# 1_MLink_V13.net
KiCad netlist of a schematic drawn in Altium Designer
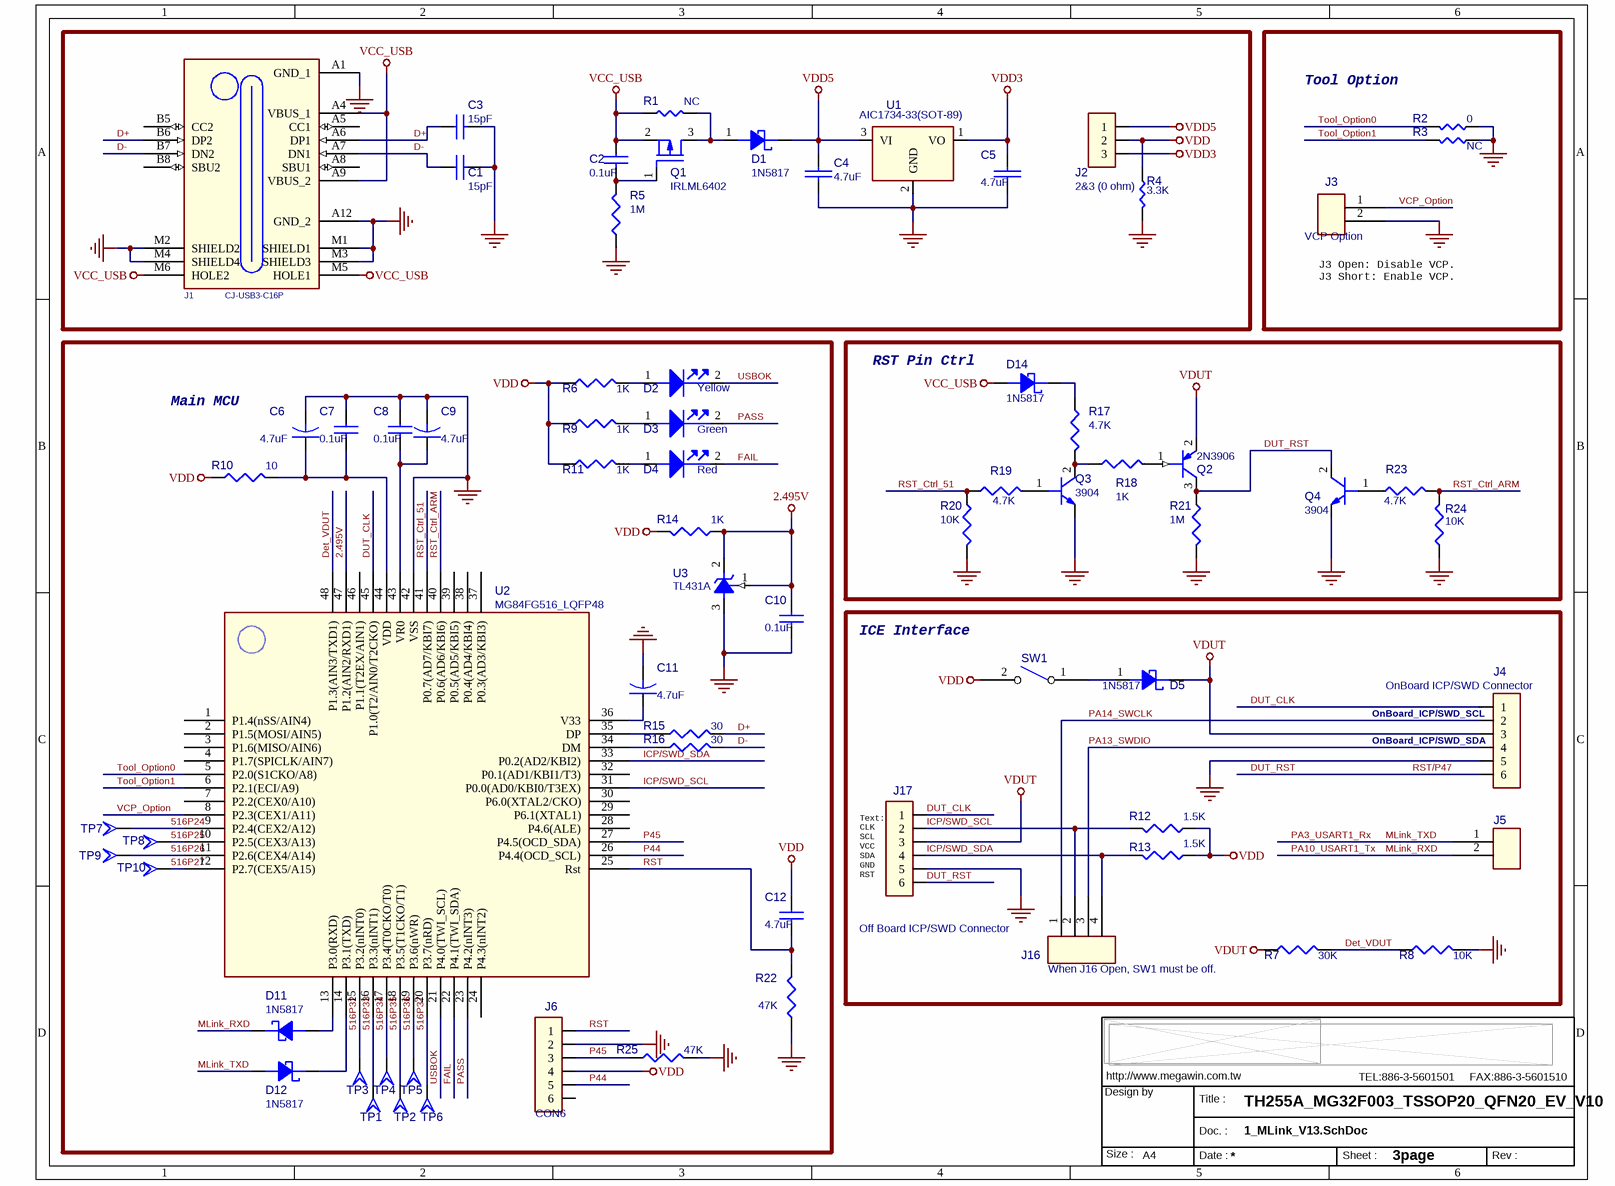
[diagram p0: 1_MLink_V13.SchDoc]

(export (version "E")
  (design (tool "Eeschema 10.0.6"))
  (components
    (comp (ref "C1") (value "15pF") (footprint "0603C") (libsource (lib "") (part "CAP NP_Dup1_1")))
    (comp (ref "C2") (value "0.1uF") (footprint "0603C") (libsource (lib "*") (part "CAP NP")))
    (comp (ref "C3") (value "15pF") (footprint "0603C") (libsource (lib "*") (part "CAP NP_Dup1")))
    (comp (ref "C4") (value "4.7uF") (footprint "0805C") (libsource (lib "*") (part "C NP")))
    (comp (ref "C5") (value "4.7uF") (footprint "0805C") (libsource (lib "*") (part "C NP")))
    (comp (ref "C6") (value "4.7uF") (libsource (lib "*") (part "CAP")))
    (comp (ref "C7") (value "0.1uF") (footprint "0603C") (libsource (lib "*") (part "CAP NP_Dup1")))
    (comp (ref "C8") (value "0.1uF") (footprint "0603C") (libsource (lib "*") (part "CAP NP")))
    (comp (ref "C9") (value "4.7uF") (libsource (lib "") (part "CAP_1")))
    (comp (ref "C10") (value "0.1uF") (footprint "0603C") (libsource (lib "*") (part "CAP NP")))
    (comp (ref "C11") (value "4.7uF") (footprint "0805C") (libsource (lib "") (part "CAP_1")))
    (comp (ref "C12") (value "4.7uF") (footprint "0805C") (libsource (lib "*") (part "CAP NP_Dup1")))
    (comp (ref "D1")
      (value "1N5817")
      (footprint "DIODE_SMA_SOD323")
      (libsource (lib "") (part "DIODE SCHOTTKY_1"))
    )
    (comp (ref "D2") (value "Yellow") (libsource (lib "*") (part "Led0_0")))
    (comp (ref "D3") (value "Green") (libsource (lib "*") (part "Led0_0")))
    (comp (ref "D4") (value "Red") (libsource (lib "*") (part "Led0_0")))
    (comp (ref "D5")
      (value "1N5817")
      (footprint "DIODE_SMA_SOD323")
      (libsource (lib "") (part "DIODE SCHOTTKY_1"))
    )
    (comp (ref "D11")
      (value "1N5817")
      (footprint "DIODE_SMA_SOD323")
      (libsource (lib "*") (part "DIODE SCHOTTKY"))
    )
    (comp (ref "D12")
      (value "1N5817")
      (footprint "DIODE_SMA_SOD323")
      (libsource (lib "*") (part "DIODE SCHOTTKY"))
    )
    (comp (ref "D14")
      (value "1N5817")
      (footprint "DIODE_SMA_SOD323")
      (libsource (lib "*") (part "DIODE SCHOTTKY"))
    )
    (comp (ref "J1")
      (value "CJ-USB3-C16P")
      (footprint "USB_CF_16_SMD")
      (description "TPYE-C-9")
      (libsource (lib "*") (part "CJ-USB3-C16P"))
    )
    (comp (ref "J2") (value "2&3 (0 ohm)") (footprint "PS3P254") (libsource (lib "*") (part "CON3")))
    (comp (ref "J3") (value "VCP Option") (footprint "PS2P254") (libsource (lib "*") (part "CON2")))
    (comp (ref "J4")
      (value "OnBoard ICP/SWD Connector")
      (footprint "PS6P254")
      (libsource (lib "*") (part "CON6"))
    )
    (comp (ref "J5") (value "NC") (footprint "PS2P254") (libsource (lib "") (part "CON2_1")))
    (comp (ref "J6") (value "CON6") (footprint "PS6P254") (libsource (lib "") (part "CON6_1")))
    (comp (ref "J16")
      (value "When J16 Open, SW1 must be off.")
      (footprint "PS4P254")
      (libsource (lib "*") (part "CON4"))
    )
    (comp (ref "J17")
      (value "Off Board ICP/SWD Connector")
      (footprint "PS6P254_90")
      (libsource (lib "") (part "CON6_1"))
    )
    (comp (ref "MW1")
      (value "MW-A4")
      (footprint "MEGAWIN_3.4_1")
      (fields
        (field (name "ORGADDR2") "http://www.megawin.com.tw")
        (field (name "ORGADDR3") "TEL:886-3-5601501     FAX:886-3-5601510")
      )
      (libsource (lib "201407_SCHLIB") (part "MW_A4_2"))
    )
    (comp (ref "Q1") (value "IRLML6402") (libsource (lib "*") (part "MOSFET P GSD")))
    (comp (ref "Q2") (value "2N3906") (footprint "SOT23") (libsource (lib "*") (part "2N3906_0")))
    (comp (ref "Q3") (value "3904") (footprint "SOT23_132") (libsource (lib "*") (part "NPN BCE")))
    (comp (ref "Q4") (value "3904") (footprint "SOT23_132") (libsource (lib "*") (part "NPN BCE")))
    (comp (ref "R1") (value "NC") (footprint "0603R") (libsource (lib "*") (part "R_Dup4")))
    (comp (ref "R2") (value "0") (footprint "0603R") (libsource (lib "*") (part "R_Dup4")))
    (comp (ref "R3") (value "NC") (footprint "0603R") (libsource (lib "*") (part "R_Dup4")))
    (comp (ref "R4") (value "3.3K") (footprint "0603R") (libsource (lib "*") (part "R_Dup4")))
    (comp (ref "R5") (value "1M") (footprint "0603R") (libsource (lib "*") (part "R_Dup2")))
    (comp (ref "R6") (value "1K") (footprint "0603R") (libsource (lib "*") (part "R_Dup2")))
    (comp (ref "R7") (value "30K") (footprint "0603R") (libsource (lib "*") (part "R_Dup2")))
    (comp (ref "R8") (value "10K") (footprint "0603R") (libsource (lib "*") (part "R_Dup2")))
    (comp (ref "R9") (value "1K") (footprint "0603R") (libsource (lib "*") (part "R_Dup2")))
    (comp (ref "R10") (value "10") (footprint "0603R") (libsource (lib "*") (part "R_Dup5")))
    (comp (ref "R11") (value "1K") (footprint "0603R") (libsource (lib "*") (part "R_Dup2")))
    (comp (ref "R12") (value "1.5K") (footprint "0603R") (libsource (lib "*") (part "R_Dup2")))
    (comp (ref "R13") (value "1.5K") (footprint "0603R") (libsource (lib "*") (part "R_Dup2")))
    (comp (ref "R14") (value "1K") (footprint "0603R") (libsource (lib "*") (part "R_Dup5")))
    (comp (ref "R15") (value "30") (footprint "0603R") (libsource (lib "*") (part "R_Dup5")))
    (comp (ref "R16") (value "30") (footprint "0603R") (libsource (lib "*") (part "R_Dup5")))
    (comp (ref "R17") (value "4.7K") (footprint "0603R") (libsource (lib "*") (part "R_Dup2")))
    (comp (ref "R18") (value "1K") (footprint "0603R") (libsource (lib "*") (part "R_Dup2")))
    (comp (ref "R19") (value "4.7K") (footprint "0603R") (libsource (lib "*") (part "R_Dup2")))
    (comp (ref "R20") (value "10K") (footprint "0603R") (libsource (lib "*") (part "R_Dup1")))
    (comp (ref "R21") (value "1M") (footprint "0603R") (libsource (lib "*") (part "R_Dup1")))
    (comp (ref "R22") (value "47K") (footprint "0603R") (libsource (lib "*") (part "R_Dup2")))
    (comp (ref "R23") (value "4.7K") (footprint "0603R") (libsource (lib "*") (part "R_Dup2")))
    (comp (ref "R24") (value "10K") (footprint "0603R") (libsource (lib "*") (part "R_Dup1")))
    (comp (ref "R25") (value "47K") (footprint "0603R") (libsource (lib "*") (part "R_Dup2")))
    (comp (ref "SW1") (value "SW KEY-SPST") (libsource (lib "*") (part "SW KEY-SPST")))
    (comp (ref "TP1") (value "T POINT A") (footprint "PIN1_1H0") (libsource (lib "*") (part "T POINT A")))
    (comp (ref "TP2") (value "T POINT A") (footprint "PIN1_1H0") (libsource (lib "*") (part "T POINT A")))
    (comp (ref "TP3") (value "T POINT A") (footprint "PIN1_1H0") (libsource (lib "*") (part "T POINT A")))
    (comp (ref "TP4") (value "T POINT A") (footprint "PIN1_1H0") (libsource (lib "*") (part "T POINT A")))
    (comp (ref "TP5") (value "T POINT A") (footprint "PIN1_1H0") (libsource (lib "*") (part "T POINT A")))
    (comp (ref "TP6") (value "T POINT A") (footprint "PIN1_1H0") (libsource (lib "*") (part "T POINT A")))
    (comp (ref "TP7") (value "T POINT A") (footprint "PIN1_1H0") (libsource (lib "*") (part "T POINT A")))
    (comp (ref "TP8") (value "T POINT A") (footprint "PIN1_1H0") (libsource (lib "*") (part "T POINT A")))
    (comp (ref "TP9") (value "T POINT A") (footprint "PIN1_1H0") (libsource (lib "*") (part "T POINT A")))
    (comp (ref "TP10") (value "T POINT A") (footprint "PIN1_1H0") (libsource (lib "*") (part "T POINT A")))
    (comp (ref "U1") (value "AIC1734-33(SOT-89)") (libsource (lib "*") (part "AIC1722-33")))
    (comp (ref "U2")
      (value "MG84FG516_LQFP48")
      (footprint "LQFP48_7X7_050")
      (libsource (lib "*") (part "MG84FG516_LQFP48"))
    )
    (comp (ref "U3") (value "TL431A") (footprint "SOT23") (libsource (lib "*") (part "TL431/CYL")))
  )
  (nets
    (net (code "1") (name "/516P24") (class "Default")
      (node (ref "TP7") (pin "1") (pinfunction "TP_1") (pintype "passive"))
      (node (ref "U2") (pin "9") (pinfunction "P2.4(CEX2/A12)_9") (pintype "passive"))
    )
    (net (code "2") (name "/516P25") (class "Default")
      (node (ref "TP8") (pin "1") (pinfunction "TP_1") (pintype "passive"))
      (node (ref "U2") (pin "10") (pinfunction "P2.5(CEX3/A13)_10") (pintype "passive"))
    )
    (net (code "3") (name "/516P26") (class "Default")
      (node (ref "TP9") (pin "1") (pinfunction "TP_1") (pintype "passive"))
      (node (ref "U2") (pin "11") (pinfunction "P2.6(CEX4/A14)_11") (pintype "passive"))
    )
    (net (code "4") (name "/516P27") (class "Default")
      (node (ref "TP10") (pin "1") (pinfunction "TP_1") (pintype "passive"))
      (node (ref "U2") (pin "12") (pinfunction "P2.7(CEX5/A15)_12") (pintype "passive"))
    )
    (net (code "5") (name "/516P32") (class "Default")
      (node (ref "TP3") (pin "1") (pinfunction "TP_1") (pintype "passive"))
      (node (ref "U2") (pin "15") (pinfunction "P3.2(nINT0)_15") (pintype "passive"))
    )
    (net (code "6") (name "/516P33") (class "Default")
      (node (ref "TP1") (pin "1") (pinfunction "TP_1") (pintype "passive"))
      (node (ref "U2") (pin "16") (pinfunction "P3.3(nINT1)_16") (pintype "passive"))
    )
    (net (code "7") (name "/516P34") (class "Default")
      (node (ref "TP4") (pin "1") (pinfunction "TP_1") (pintype "passive"))
      (node (ref "U2") (pin "17") (pinfunction "P3.4(T0CKO/T0)_17") (pintype "passive"))
    )
    (net (code "8") (name "/516P35") (class "Default")
      (node (ref "TP2") (pin "1") (pinfunction "TP_1") (pintype "passive"))
      (node (ref "U2") (pin "18") (pinfunction "P3.5(T1CKO/T1)_18") (pintype "passive"))
    )
    (net (code "9") (name "/516P36") (class "Default")
      (node (ref "TP5") (pin "1") (pinfunction "TP_1") (pintype "passive"))
      (node (ref "U2") (pin "19") (pinfunction "P3.6(nWR)_19") (pintype "passive"))
    )
    (net (code "10") (name "/516P37") (class "Default")
      (node (ref "TP6") (pin "1") (pinfunction "TP_1") (pintype "passive"))
      (node (ref "U2") (pin "20") (pinfunction "P3.7(nRD)_20") (pintype "passive"))
    )
    (net (code "11") (name "/D+") (class "Default")
      (node (ref "C3") (pin "1") (pinfunction "1_1") (pintype "passive"))
      (node (ref "J1") (pin "A6") (pinfunction "DP1_A6") (pintype "input"))
      (node (ref "J1") (pin "B6") (pinfunction "DP2_B6") (pintype "input"))
      (node (ref "R15") (pin "2") (pinfunction "2_2") (pintype "passive"))
    )
    (net (code "12") (name "/D-") (class "Default")
      (node (ref "C1") (pin "1") (pinfunction "1_1") (pintype "passive"))
      (node (ref "J1") (pin "A7") (pinfunction "DN1_A7") (pintype "input"))
      (node (ref "J1") (pin "B7") (pinfunction "DN2_B7") (pintype "input"))
      (node (ref "R16") (pin "2") (pinfunction "2_2") (pintype "passive"))
    )
    (net (code "13") (name "/DUT_CLK") (class "Default")
      (node (ref "J17") (pin "1") (pinfunction "1_1") (pintype "passive"))
      (node (ref "J4") (pin "1") (pinfunction "1_1") (pintype "passive"))
      (node (ref "U2") (pin "45") (pinfunction "P1.0(T2/AIN0/T2CKO)_45") (pintype "passive"))
    )
    (net (code "14") (name "/DUT_RST") (class "Default")
      (node (ref "J17") (pin "6") (pinfunction "6_6") (pintype "passive"))
      (node (ref "J4") (pin "6") (pinfunction "6_6") (pintype "passive"))
      (node (ref "Q2") (pin "3") (pinfunction "COLLECTOR_3") (pintype "passive"))
      (node (ref "Q4") (pin "2") (pinfunction "C_2") (pintype "passive"))
      (node (ref "R21") (pin "1") (pinfunction "1_1") (pintype "passive"))
    )
    (net (code "15") (name "/Det_VDUT") (class "Default")
      (node (ref "R7") (pin "2") (pinfunction "2_2") (pintype "passive"))
      (node (ref "R8") (pin "1") (pinfunction "1_1") (pintype "passive"))
      (node (ref "U2") (pin "48") (pinfunction "P1.3(AIN3/TXD1)_48") (pintype "passive"))
    )
    (net (code "16") (name "/FAIL") (class "Default")
      (node (ref "D4") (pin "2") (pinfunction "2_2") (pintype "passive"))
      (node (ref "U2") (pin "22") (pinfunction "P4.1(TWI_SDA)_22") (pintype "passive"))
    )
    (net (code "17") (name "/ICP{slash}SWD_SCL") (class "Default")
      (node (ref "J16") (pin "2") (pinfunction "2_2") (pintype "passive"))
      (node (ref "J17") (pin "2") (pinfunction "2_2") (pintype "passive"))
      (node (ref "R12") (pin "2") (pinfunction "2_2") (pintype "passive"))
      (node (ref "U2") (pin "31") (pinfunction "P0.0(AD0/KBI0/T3EX)_31") (pintype "passive"))
    )
    (net (code "18") (name "/ICP{slash}SWD_SDA") (class "Default")
      (node (ref "J16") (pin "4") (pinfunction "4_4") (pintype "passive"))
      (node (ref "J17") (pin "4") (pinfunction "4_4") (pintype "passive"))
      (node (ref "R13") (pin "2") (pinfunction "2_2") (pintype "passive"))
      (node (ref "U2") (pin "33") (pinfunction "P0.2(AD2/KBI2)_33") (pintype "passive"))
    )
    (net (code "19") (name "/MLink_RXD") (class "Default")
      (node (ref "D11") (pin "2") (pinfunction "CATHODE_2") (pintype "passive"))
      (node (ref "J5") (pin "2") (pinfunction "2_2") (pintype "passive"))
    )
    (net (code "20") (name "/MLink_TXD") (class "Default")
      (node (ref "D12") (pin "1") (pinfunction "ANODE_1") (pintype "passive"))
      (node (ref "J5") (pin "1") (pinfunction "1_1") (pintype "passive"))
    )
    (net (code "21") (name "/P44") (class "Default")
      (node (ref "J6") (pin "5") (pinfunction "5_5") (pintype "passive"))
      (node (ref "U2") (pin "26") (pinfunction "P4.4(OCD_SCL)_26") (pintype "passive"))
    )
    (net (code "22") (name "/P45") (class "Default")
      (node (ref "J6") (pin "3") (pinfunction "3_3") (pintype "passive"))
      (node (ref "R25") (pin "1") (pinfunction "1_1") (pintype "passive"))
      (node (ref "U2") (pin "27") (pinfunction "P4.5(OCD_SDA)_27") (pintype "passive"))
    )
    (net (code "23") (name "/PA13_SWDIO") (class "Default")
      (node (ref "J16") (pin "3") (pinfunction "3_3") (pintype "passive"))
      (node (ref "J4") (pin "4") (pinfunction "4_4") (pintype "passive"))
    )
    (net (code "24") (name "/PA14_SWCLK") (class "Default")
      (node (ref "J16") (pin "1") (pinfunction "1_1") (pintype "passive"))
      (node (ref "J4") (pin "2") (pinfunction "2_2") (pintype "passive"))
    )
    (net (code "25") (name "/PASS") (class "Default")
      (node (ref "D3") (pin "2") (pinfunction "2_2") (pintype "passive"))
      (node (ref "U2") (pin "23") (pinfunction "P4.2(nINT3)_23") (pintype "passive"))
    )
    (net (code "26") (name "/RST") (class "Default")
      (node (ref "C12") (pin "2") (pinfunction "2_2") (pintype "passive"))
      (node (ref "J6") (pin "1") (pinfunction "1_1") (pintype "passive"))
      (node (ref "R22") (pin "2") (pinfunction "2_2") (pintype "passive"))
      (node (ref "U2") (pin "25") (pinfunction "Rst_25") (pintype "passive"))
    )
    (net (code "27") (name "/RST_Ctrl_51") (class "Default")
      (node (ref "R19") (pin "1") (pinfunction "1_1") (pintype "passive"))
      (node (ref "R20") (pin "1") (pinfunction "1_1") (pintype "passive"))
      (node (ref "U2") (pin "41") (pinfunction "P0.7(AD7/KBI7)_41") (pintype "passive"))
    )
    (net (code "28") (name "/RST_Ctrl_ARM") (class "Default")
      (node (ref "R23") (pin "1") (pinfunction "1_1") (pintype "passive"))
      (node (ref "R24") (pin "1") (pinfunction "1_1") (pintype "passive"))
      (node (ref "U2") (pin "40") (pinfunction "P0.6(AD6/KBI6)_40") (pintype "passive"))
    )
    (net (code "29") (name "/Tool_Option0") (class "Default")
      (node (ref "R2") (pin "1") (pinfunction "1_1") (pintype "passive"))
      (node (ref "U2") (pin "5") (pinfunction "P2.0(S1CKO/A8)_5") (pintype "passive"))
    )
    (net (code "30") (name "/Tool_Option1") (class "Default")
      (node (ref "R3") (pin "1") (pinfunction "1_1") (pintype "passive"))
      (node (ref "U2") (pin "6") (pinfunction "P2.1(ECI/A9)_6") (pintype "passive"))
    )
    (net (code "31") (name "/USBOK") (class "Default")
      (node (ref "D2") (pin "2") (pinfunction "2_2") (pintype "passive"))
      (node (ref "U2") (pin "21") (pinfunction "P4.0(TWI_SCL)_21") (pintype "passive"))
    )
    (net (code "32") (name "/VCP_Option") (class "Default")
      (node (ref "J3") (pin "1") (pinfunction "1_1") (pintype "passive"))
      (node (ref "U2") (pin "8") (pinfunction "P2.3(CEX1/A11)_8") (pintype "passive"))
    )
    (net (code "33") (name "2.495V") (class "Default")
      (node (ref "C10") (pin "1") (pinfunction "1_1") (pintype "passive"))
      (node (ref "R14") (pin "1") (pinfunction "1_1") (pintype "passive"))
      (node (ref "U2") (pin "47") (pinfunction "P1.2(AIN2/RXD1)_47") (pintype "passive"))
      (node (ref "U3") (pin "1") (pinfunction "VREF_1") (pintype "input"))
      (node (ref "U3") (pin "2") (pinfunction "C_2") (pintype "passive"))
    )
    (net (code "34") (name "GND_POWER") (class "Default")
      (node (ref "C1") (pin "2") (pinfunction "2_2") (pintype "passive"))
      (node (ref "C10") (pin "2") (pinfunction "2_2") (pintype "passive"))
      (node (ref "C11") (pin "2") (pinfunction "2_2") (pintype "passive"))
      (node (ref "C3") (pin "2") (pinfunction "2_2") (pintype "passive"))
      (node (ref "C4") (pin "2") (pinfunction "2_2") (pintype "passive"))
      (node (ref "C5") (pin "2") (pinfunction "2_2") (pintype "passive"))
      (node (ref "C6") (pin "2") (pinfunction "2_2") (pintype "passive"))
      (node (ref "C7") (pin "1") (pinfunction "1_1") (pintype "passive"))
      (node (ref "C8") (pin "1") (pinfunction "1_1") (pintype "passive"))
      (node (ref "C9") (pin "2") (pinfunction "2_2") (pintype "passive"))
      (node (ref "J1") (pin "A1") (pinfunction "GND_1_A1") (pintype "power_in"))
      (node (ref "J1") (pin "A12") (pinfunction "GND_2_A12") (pintype "power_in"))
      (node (ref "J1") (pin "M1") (pinfunction "SHIELD1_M1") (pintype "power_in"))
      (node (ref "J1") (pin "M2") (pinfunction "SHIELD2_M2") (pintype "power_in"))
      (node (ref "J1") (pin "M3") (pinfunction "SHIELD3_M3") (pintype "power_in"))
      (node (ref "J1") (pin "M4") (pinfunction "SHIELD4_M4") (pintype "power_in"))
      (node (ref "J17") (pin "5") (pinfunction "5_5") (pintype "passive"))
      (node (ref "J3") (pin "2") (pinfunction "2_2") (pintype "passive"))
      (node (ref "J4") (pin "5") (pinfunction "5_5") (pintype "passive"))
      (node (ref "J6") (pin "2") (pinfunction "2_2") (pintype "passive"))
      (node (ref "Q3") (pin "3") (pinfunction "E_3") (pintype "passive"))
      (node (ref "Q4") (pin "3") (pinfunction "E_3") (pintype "passive"))
      (node (ref "R2") (pin "2") (pinfunction "2_2") (pintype "passive"))
      (node (ref "R20") (pin "2") (pinfunction "2_2") (pintype "passive"))
      (node (ref "R21") (pin "2") (pinfunction "2_2") (pintype "passive"))
      (node (ref "R22") (pin "1") (pinfunction "1_1") (pintype "passive"))
      (node (ref "R24") (pin "2") (pinfunction "2_2") (pintype "passive"))
      (node (ref "R25") (pin "2") (pinfunction "2_2") (pintype "passive"))
      (node (ref "R3") (pin "2") (pinfunction "2_2") (pintype "passive"))
      (node (ref "R4") (pin "2") (pinfunction "2_2") (pintype "passive"))
      (node (ref "R5") (pin "1") (pinfunction "1_1") (pintype "passive"))
      (node (ref "R8") (pin "2") (pinfunction "2_2") (pintype "passive"))
      (node (ref "U1") (pin "2") (pinfunction "GND_2") (pintype "passive"))
      (node (ref "U2") (pin "42") (pinfunction "VSS_42") (pintype "passive"))
      (node (ref "U3") (pin "3") (pinfunction "A_3") (pintype "passive"))
    )
    (net (code "35") (name "Net-(D1-ANODE)") (class "Default")
      (node (ref "D1") (pin "1") (pinfunction "ANODE_1") (pintype "passive"))
      (node (ref "Q1") (pin "3") (pinfunction "D_3") (pintype "passive"))
      (node (ref "R1") (pin "2") (pinfunction "2_2") (pintype "passive"))
    )
    (net (code "36") (name "Net-(D2-Pad1)") (class "Default")
      (node (ref "D2") (pin "1") (pinfunction "1_1") (pintype "passive"))
      (node (ref "R6") (pin "2") (pinfunction "2_2") (pintype "passive"))
    )
    (net (code "37") (name "Net-(D3-Pad1)") (class "Default")
      (node (ref "D3") (pin "1") (pinfunction "1_1") (pintype "passive"))
      (node (ref "R9") (pin "2") (pinfunction "2_2") (pintype "passive"))
    )
    (net (code "38") (name "Net-(D4-Pad1)") (class "Default")
      (node (ref "D4") (pin "1") (pinfunction "1_1") (pintype "passive"))
      (node (ref "R11") (pin "2") (pinfunction "2_2") (pintype "passive"))
    )
    (net (code "39") (name "Net-(D5-ANODE)") (class "Default")
      (node (ref "D5") (pin "1") (pinfunction "ANODE_1") (pintype "passive"))
      (node (ref "SW1") (pin "1") (pinfunction "1_1") (pintype "passive"))
    )
    (net (code "40") (name "Net-(D11-ANODE)") (class "Default")
      (node (ref "D11") (pin "1") (pinfunction "ANODE_1") (pintype "passive"))
      (node (ref "U2") (pin "13") (pinfunction "P3.0(RXD)_13") (pintype "passive"))
    )
    (net (code "41") (name "Net-(D12-CATHODE)") (class "Default")
      (node (ref "D12") (pin "2") (pinfunction "CATHODE_2") (pintype "passive"))
      (node (ref "U2") (pin "14") (pinfunction "P3.1(TXD)_14") (pintype "passive"))
    )
    (net (code "42") (name "Net-(D14-CATHODE)") (class "Default")
      (node (ref "D14") (pin "2") (pinfunction "CATHODE_2") (pintype "passive"))
      (node (ref "R17") (pin "1") (pinfunction "1_1") (pintype "passive"))
    )
    (net (code "43") (name "Net-(Q1-G)") (class "Default")
      (node (ref "C2") (pin "2") (pinfunction "2_2") (pintype "passive"))
      (node (ref "Q1") (pin "1") (pinfunction "G_1") (pintype "passive"))
      (node (ref "R5") (pin "2") (pinfunction "2_2") (pintype "passive"))
    )
    (net (code "44") (name "Net-(Q2-BASE)") (class "Default")
      (node (ref "Q2") (pin "1") (pinfunction "BASE_1") (pintype "input"))
      (node (ref "R18") (pin "2") (pinfunction "2_2") (pintype "passive"))
    )
    (net (code "45") (name "Net-(Q3-B)") (class "Default")
      (node (ref "Q3") (pin "1") (pinfunction "B_1") (pintype "passive"))
      (node (ref "R19") (pin "2") (pinfunction "2_2") (pintype "passive"))
    )
    (net (code "46") (name "Net-(Q3-C)") (class "Default")
      (node (ref "Q3") (pin "2") (pinfunction "C_2") (pintype "passive"))
      (node (ref "R17") (pin "2") (pinfunction "2_2") (pintype "passive"))
      (node (ref "R18") (pin "1") (pinfunction "1_1") (pintype "passive"))
    )
    (net (code "47") (name "Net-(Q4-B)") (class "Default")
      (node (ref "Q4") (pin "1") (pinfunction "B_1") (pintype "passive"))
      (node (ref "R23") (pin "2") (pinfunction "2_2") (pintype "passive"))
    )
    (net (code "48") (name "Net-(U2-DM)") (class "Default")
      (node (ref "R16") (pin "1") (pinfunction "1_1") (pintype "passive"))
      (node (ref "U2") (pin "34") (pinfunction "DM_34") (pintype "passive"))
    )
    (net (code "49") (name "Net-(U2-DP)") (class "Default")
      (node (ref "R15") (pin "1") (pinfunction "1_1") (pintype "passive"))
      (node (ref "U2") (pin "35") (pinfunction "DP_35") (pintype "passive"))
    )
    (net (code "50") (name "Net-(U2-V33)") (class "Default")
      (node (ref "C11") (pin "1") (pinfunction "1_1") (pintype "passive"))
      (node (ref "U2") (pin "36") (pinfunction "V33_36") (pintype "passive"))
    )
    (net (code "51") (name "Net-(U2-VDD)") (class "Default")
      (node (ref "C6") (pin "1") (pinfunction "1_1") (pintype "passive"))
      (node (ref "C7") (pin "2") (pinfunction "2_2") (pintype "passive"))
      (node (ref "R10") (pin "2") (pinfunction "2_2") (pintype "passive"))
      (node (ref "U2") (pin "44") (pinfunction "VDD_44") (pintype "passive"))
    )
    (net (code "52") (name "Net-(U2-VR0)") (class "Default")
      (node (ref "C8") (pin "2") (pinfunction "2_2") (pintype "passive"))
      (node (ref "C9") (pin "1") (pinfunction "1_1") (pintype "passive"))
      (node (ref "U2") (pin "43") (pinfunction "VR0_43") (pintype "passive"))
    )
    (net (code "53") (name "VCC_USB") (class "Default")
      (node (ref "C2") (pin "1") (pinfunction "1_1") (pintype "passive"))
      (node (ref "D14") (pin "1") (pinfunction "ANODE_1") (pintype "passive"))
      (node (ref "J1") (pin "A4") (pinfunction "VBUS_1_A4") (pintype "power_in"))
      (node (ref "J1") (pin "A9") (pinfunction "VBUS_2_A9") (pintype "power_in"))
      (node (ref "J1") (pin "M5") (pinfunction "HOLE1_M5") (pintype "power_in"))
      (node (ref "J1") (pin "M6") (pinfunction "HOLE2_M6") (pintype "power_in"))
      (node (ref "Q1") (pin "2") (pinfunction "S_2") (pintype "passive"))
      (node (ref "R1") (pin "1") (pinfunction "1_1") (pintype "passive"))
    )
    (net (code "54") (name "VDD") (class "Default")
      (node (ref "C12") (pin "1") (pinfunction "1_1") (pintype "passive"))
      (node (ref "J2") (pin "2") (pinfunction "2_2") (pintype "passive"))
      (node (ref "J6") (pin "4") (pinfunction "4_4") (pintype "passive"))
      (node (ref "R10") (pin "1") (pinfunction "1_1") (pintype "passive"))
      (node (ref "R11") (pin "1") (pinfunction "1_1") (pintype "passive"))
      (node (ref "R12") (pin "1") (pinfunction "1_1") (pintype "passive"))
      (node (ref "R13") (pin "1") (pinfunction "1_1") (pintype "passive"))
      (node (ref "R14") (pin "2") (pinfunction "2_2") (pintype "passive"))
      (node (ref "R4") (pin "1") (pinfunction "1_1") (pintype "passive"))
      (node (ref "R6") (pin "1") (pinfunction "1_1") (pintype "passive"))
      (node (ref "R9") (pin "1") (pinfunction "1_1") (pintype "passive"))
      (node (ref "SW1") (pin "2") (pinfunction "2_2") (pintype "passive"))
    )
    (net (code "55") (name "VDD3") (class "Default")
      (node (ref "C5") (pin "1") (pinfunction "1_1") (pintype "passive"))
      (node (ref "J2") (pin "3") (pinfunction "3_3") (pintype "passive"))
      (node (ref "U1") (pin "1") (pinfunction "VO_1") (pintype "passive"))
    )
    (net (code "56") (name "VDD5") (class "Default")
      (node (ref "C4") (pin "1") (pinfunction "1_1") (pintype "passive"))
      (node (ref "D1") (pin "2") (pinfunction "CATHODE_2") (pintype "passive"))
      (node (ref "J2") (pin "1") (pinfunction "1_1") (pintype "passive"))
      (node (ref "U1") (pin "3") (pinfunction "VI_3") (pintype "passive"))
    )
    (net (code "57") (name "VDUT") (class "Default")
      (node (ref "D5") (pin "2") (pinfunction "CATHODE_2") (pintype "passive"))
      (node (ref "J17") (pin "3") (pinfunction "3_3") (pintype "passive"))
      (node (ref "J4") (pin "3") (pinfunction "3_3") (pintype "passive"))
      (node (ref "Q2") (pin "2") (pinfunction "EMITTER_2") (pintype "passive"))
      (node (ref "R7") (pin "1") (pinfunction "1_1") (pintype "passive"))
    )
    (net (code "58") (name "unconnected-(J1-CC1-PadA5)") (class "Default")
      (node (ref "J1") (pin "A5") (pinfunction "CC1_A5") (pintype "bidirectional"))
    )
    (net (code "59") (name "unconnected-(J1-CC2-PadB5)") (class "Default")
      (node (ref "J1") (pin "B5") (pinfunction "CC2_B5") (pintype "bidirectional"))
    )
    (net (code "60") (name "unconnected-(J1-SBU1-PadA8)") (class "Default")
      (node (ref "J1") (pin "A8") (pinfunction "SBU1_A8") (pintype "bidirectional"))
    )
    (net (code "61") (name "unconnected-(J1-SBU2-PadB8)") (class "Default")
      (node (ref "J1") (pin "B8") (pinfunction "SBU2_B8") (pintype "bidirectional"))
    )
    (net (code "62") (name "unconnected-(J6-Pad6)") (class "Default")
      (node (ref "J6") (pin "6") (pinfunction "6_6") (pintype "passive"))
    )
    (net (code "63") (name "unconnected-(U2-P0.1(AD1{slash}KBI1{slash}T3)-Pad32)") (class "Default")
      (node (ref "U2") (pin "32") (pinfunction "P0.1(AD1/KBI1/T3)_32") (pintype "passive"))
    )
    (net (code "64") (name "unconnected-(U2-P0.3(AD3{slash}KBI3)-Pad37)") (class "Default")
      (node (ref "U2") (pin "37") (pinfunction "P0.3(AD3/KBI3)_37") (pintype "passive"))
    )
    (net (code "65") (name "unconnected-(U2-P0.4(AD4{slash}KBI4)-Pad38)") (class "Default")
      (node (ref "U2") (pin "38") (pinfunction "P0.4(AD4/KBI4)_38") (pintype "passive"))
    )
    (net (code "66") (name "unconnected-(U2-P0.5(AD5{slash}KBI5)-Pad39)") (class "Default")
      (node (ref "U2") (pin "39") (pinfunction "P0.5(AD5/KBI5)_39") (pintype "passive"))
    )
    (net (code "67") (name "unconnected-(U2-P1.1(T2EX{slash}AIN1)-Pad46)") (class "Default")
      (node (ref "U2") (pin "46") (pinfunction "P1.1(T2EX/AIN1)_46") (pintype "passive"))
    )
    (net (code "68") (name "unconnected-(U2-P1.4(nSS{slash}AIN4)-Pad1)") (class "Default")
      (node (ref "U2") (pin "1") (pinfunction "P1.4(nSS/AIN4)_1") (pintype "passive"))
    )
    (net (code "69") (name "unconnected-(U2-P1.5(MOSI{slash}AIN5)-Pad2)") (class "Default")
      (node (ref "U2") (pin "2") (pinfunction "P1.5(MOSI/AIN5)_2") (pintype "passive"))
    )
    (net (code "70") (name "unconnected-(U2-P1.6(MISO{slash}AIN6)-Pad3)") (class "Default")
      (node (ref "U2") (pin "3") (pinfunction "P1.6(MISO/AIN6)_3") (pintype "passive"))
    )
    (net (code "71") (name "unconnected-(U2-P1.7(SPICLK{slash}AIN7)-Pad4)") (class "Default")
      (node (ref "U2") (pin "4") (pinfunction "P1.7(SPICLK/AIN7)_4") (pintype "passive"))
    )
    (net (code "72") (name "unconnected-(U2-P2.2(CEX0{slash}A10)-Pad7)") (class "Default")
      (node (ref "U2") (pin "7") (pinfunction "P2.2(CEX0/A10)_7") (pintype "passive"))
    )
    (net (code "73") (name "unconnected-(U2-P4.3(nINT2)-Pad24)") (class "Default")
      (node (ref "U2") (pin "24") (pinfunction "P4.3(nINT2)_24") (pintype "passive"))
    )
    (net (code "74") (name "unconnected-(U2-P4.6(ALE)-Pad28)") (class "Default")
      (node (ref "U2") (pin "28") (pinfunction "P4.6(ALE)_28") (pintype "passive"))
    )
    (net (code "75") (name "unconnected-(U2-P6.0(XTAL2{slash}CKO)-Pad30)") (class "Default")
      (node (ref "U2") (pin "30") (pinfunction "P6.0(XTAL2/CKO)_30") (pintype "passive"))
    )
    (net (code "76") (name "unconnected-(U2-P6.1(XTAL1)-Pad29)") (class "Default")
      (node (ref "U2") (pin "29") (pinfunction "P6.1(XTAL1)_29") (pintype "passive"))
    )
  )
)
